# RK3566_DDR_PHY.net
KiCad netlist of a schematic drawn in Altium Designer
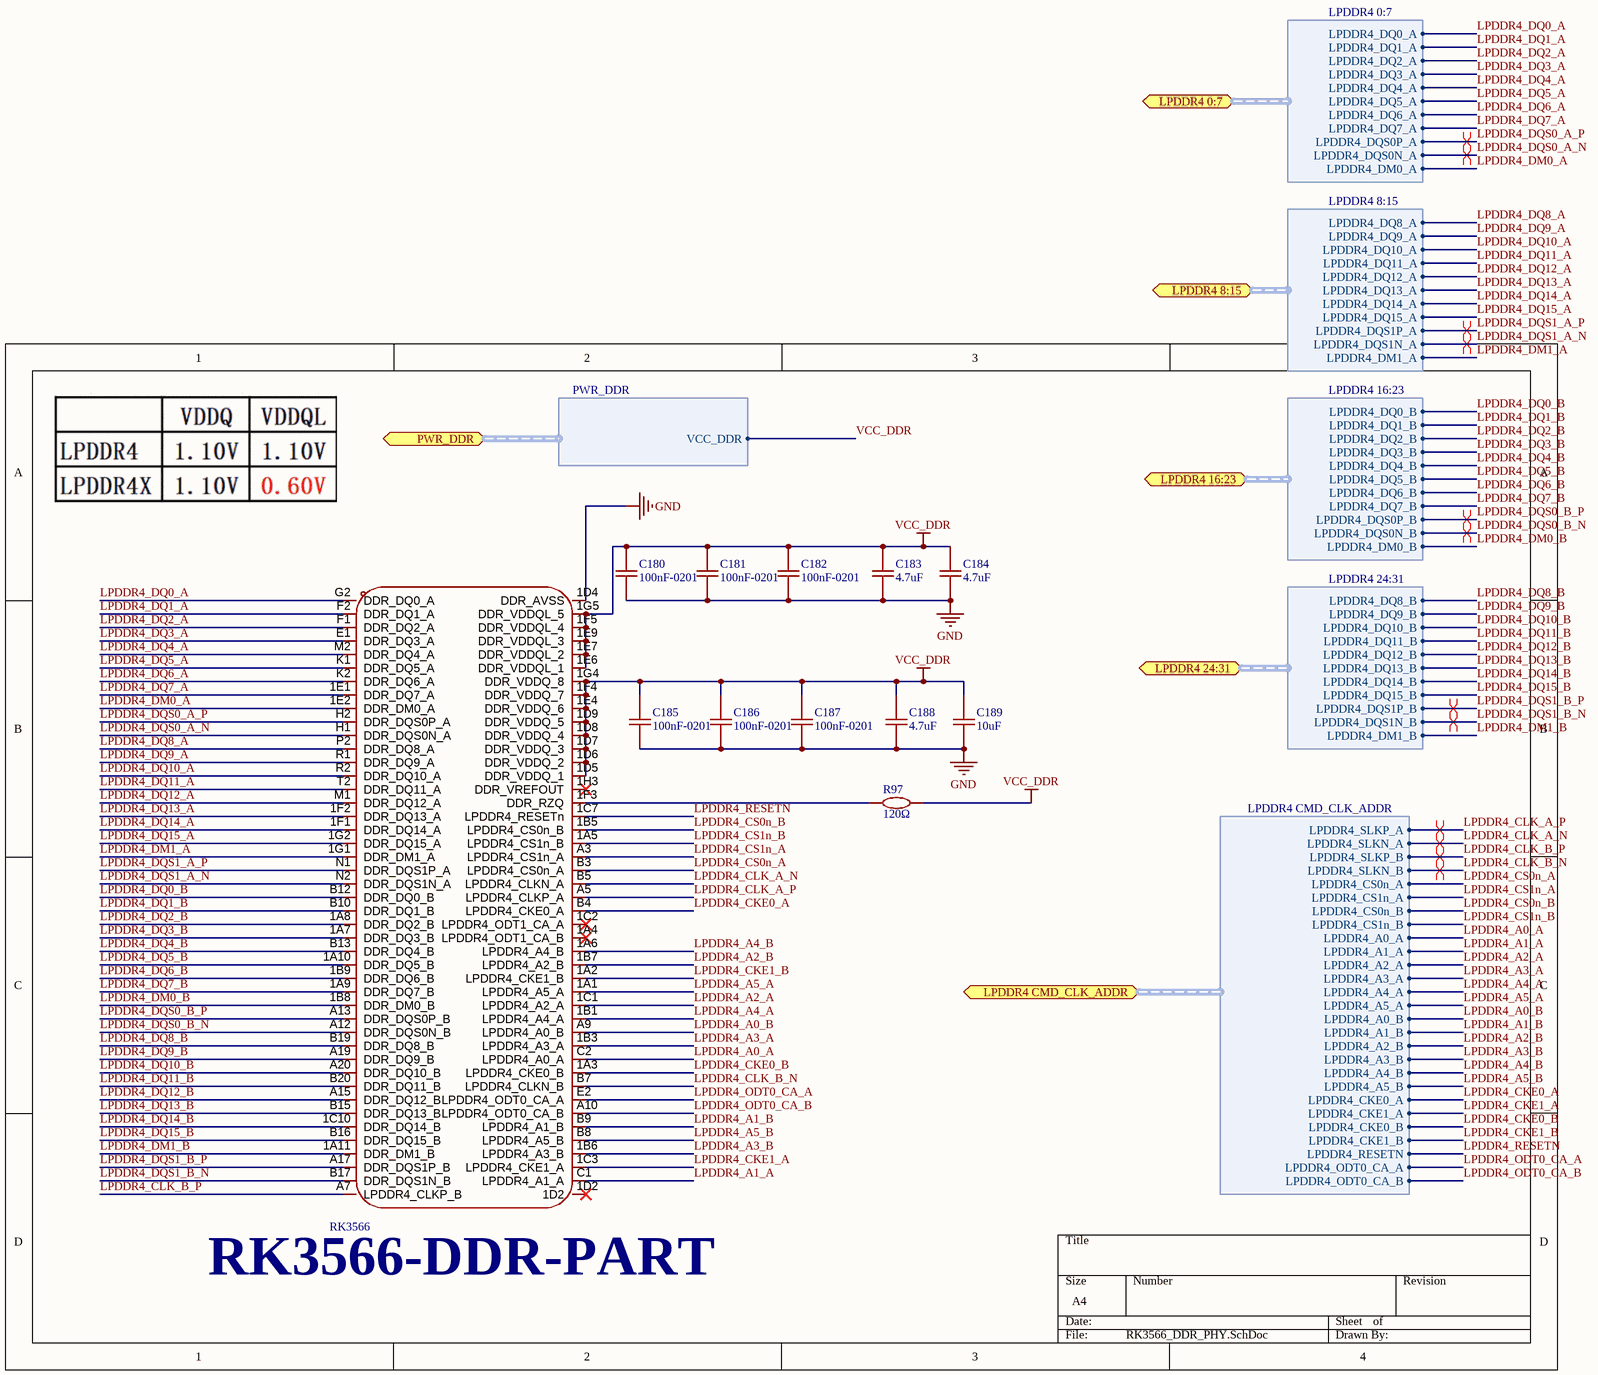
[diagram p0: RK3566_DDR_PHY.SchDoc]

(export (version "E")
  (design (tool "Eeschema 10.0.6"))
  (components
    (comp (ref "C180")
      (value "100nF-0201")
      (footprint "C0201")
      (description "CL03A104KO3NNNC")
      (libsource (lib "RLC") (part "100nF-0201"))
    )
    (comp (ref "C181")
      (value "100nF-0201")
      (footprint "C0201")
      (description "CL03A104KO3NNNC")
      (libsource (lib "RLC") (part "100nF-0201"))
    )
    (comp (ref "C182")
      (value "100nF-0201")
      (footprint "C0201")
      (description "CL03A104KO3NNNC")
      (libsource (lib "RLC") (part "100nF-0201"))
    )
    (comp (ref "C183")
      (value "4.7uF")
      (footprint "C0402")
      (description "10V 4.7uF X5R ±20% 0402 Ceramic Capacitors ROHS")
      (libsource (lib "RLC") (part "4.7uF"))
    )
    (comp (ref "C184")
      (value "4.7uF")
      (footprint "C0402")
      (description "10V 4.7uF X5R ±20% 0402 Ceramic Capacitors ROHS")
      (libsource (lib "RLC") (part "4.7uF"))
    )
    (comp (ref "C185")
      (value "100nF-0201")
      (footprint "C0201")
      (description "CL03A104KO3NNNC")
      (libsource (lib "RLC") (part "100nF-0201"))
    )
    (comp (ref "C186")
      (value "100nF-0201")
      (footprint "C0201")
      (description "CL03A104KO3NNNC")
      (libsource (lib "RLC") (part "100nF-0201"))
    )
    (comp (ref "C187")
      (value "100nF-0201")
      (footprint "C0201")
      (description "CL03A104KO3NNNC")
      (libsource (lib "RLC") (part "100nF-0201"))
    )
    (comp (ref "C188")
      (value "4.7uF")
      (footprint "C0402")
      (description "10V 4.7uF X5R ±20% 0402 Ceramic Capacitors ROHS")
      (libsource (lib "RLC") (part "4.7uF"))
    )
    (comp (ref "C189")
      (value "10uF")
      (footprint "C0603")
      (description "10V 10uF X5R ±10% 0603 Ceramic Capacitors ROHS")
      (libsource (lib "RLC") (part "10uF"))
    )
    (comp (ref "R97")
      (value "120Ω")
      (footprint "R0402")
      (description "62.5mW 120Ω 50V ±100ppm/℃ Thick Film Resistor ±1% 0402 Chip Resistor - Surface Mount ROHS")
      (libsource (lib "RLC") (part "120Ω"))
    )
    (comp (ref "U2")
      (value "RK3566")
      (footprint "BGA-565_L15.5-W14.4-P0.40_RK3566_1")
      (description "BGA-565(15.5x14.4)")
      (libsource (lib "IC") (part "RK3566"))
    )
  )
  (nets
    (net (code "8") (name "/LPDDR4_A0_A") (class "Default")
      (node (ref "U2") (pin "C2") (pinfunction "LPDDR4_A0_A_C2") (pintype "passive"))
    )
    (net (code "9") (name "/LPDDR4_A0_B") (class "Default")
      (node (ref "U2") (pin "A9") (pinfunction "LPDDR4_A0_B_A9") (pintype "passive"))
    )
    (net (code "10") (name "/LPDDR4_A1_A") (class "Default")
      (node (ref "U2") (pin "C1") (pinfunction "LPDDR4_A1_A_C1") (pintype "passive"))
    )
    (net (code "11") (name "/LPDDR4_A1_B") (class "Default")
      (node (ref "U2") (pin "B9") (pinfunction "LPDDR4_A1_B_B9") (pintype "passive"))
    )
    (net (code "12") (name "/LPDDR4_A2_A") (class "Default")
      (node (ref "U2") (pin "1C1") (pinfunction "LPDDR4_A2_A_1C1") (pintype "passive"))
    )
    (net (code "13") (name "/LPDDR4_A2_B") (class "Default")
      (node (ref "U2") (pin "1B7") (pinfunction "LPDDR4_A2_B_1B7") (pintype "passive"))
    )
    (net (code "14") (name "/LPDDR4_A3_A") (class "Default")
      (node (ref "U2") (pin "1B3") (pinfunction "LPDDR4_A3_A_1B3") (pintype "passive"))
    )
    (net (code "15") (name "/LPDDR4_A3_B") (class "Default")
      (node (ref "U2") (pin "1B6") (pinfunction "LPDDR4_A3_B_1B6") (pintype "passive"))
    )
    (net (code "16") (name "/LPDDR4_A4_A") (class "Default")
      (node (ref "U2") (pin "1B1") (pinfunction "LPDDR4_A4_A_1B1") (pintype "passive"))
    )
    (net (code "17") (name "/LPDDR4_A4_B") (class "Default")
      (node (ref "U2") (pin "1A6") (pinfunction "LPDDR4_A4_B_1A6") (pintype "passive"))
    )
    (net (code "18") (name "/LPDDR4_A5_A") (class "Default")
      (node (ref "U2") (pin "1A1") (pinfunction "LPDDR4_A5_A_1A1") (pintype "passive"))
    )
    (net (code "19") (name "/LPDDR4_A5_B") (class "Default")
      (node (ref "U2") (pin "B8") (pinfunction "LPDDR4_A5_B_B8") (pintype "passive"))
    )
    (net (code "20") (name "/LPDDR4_CKE0_A") (class "Default")
      (node (ref "U2") (pin "B4") (pinfunction "LPDDR4_CKE0_A_B4") (pintype "passive"))
    )
    (net (code "21") (name "/LPDDR4_CKE0_B") (class "Default")
      (node (ref "U2") (pin "1A3") (pinfunction "LPDDR4_CKE0_B_1A3") (pintype "passive"))
    )
    (net (code "22") (name "/LPDDR4_CKE1_A") (class "Default")
      (node (ref "U2") (pin "1C3") (pinfunction "LPDDR4_CKE1_A_1C3") (pintype "passive"))
    )
    (net (code "23") (name "/LPDDR4_CKE1_B") (class "Default")
      (node (ref "U2") (pin "1A2") (pinfunction "LPDDR4_CKE1_B_1A2") (pintype "passive"))
    )
    (net (code "24") (name "/LPDDR4_CLK_A_N") (class "Default")
      (node (ref "U2") (pin "B5") (pinfunction "LPDDR4_CLKN_A_B5") (pintype "passive"))
    )
    (net (code "25") (name "/LPDDR4_CLK_A_P") (class "Default")
      (node (ref "U2") (pin "A5") (pinfunction "LPDDR4_CLKP_A_A5") (pintype "passive"))
    )
    (net (code "26") (name "/LPDDR4_CLK_B_N") (class "Default")
      (node (ref "U2") (pin "B7") (pinfunction "LPDDR4_CLKN_B_B7") (pintype "passive"))
    )
    (net (code "27") (name "/LPDDR4_CLK_B_P") (class "Default")
      (node (ref "U2") (pin "A7") (pinfunction "LPDDR4_CLKP_B_A7") (pintype "passive"))
    )
    (net (code "28") (name "/LPDDR4_CS0n_A") (class "Default")
      (node (ref "U2") (pin "B3") (pinfunction "LPDDR4_CS0n_A_B3") (pintype "passive"))
    )
    (net (code "29") (name "/LPDDR4_CS0n_B") (class "Default")
      (node (ref "U2") (pin "1B5") (pinfunction "LPDDR4_CS0n_B_1B5") (pintype "passive"))
    )
    (net (code "30") (name "/LPDDR4_CS1n_A") (class "Default")
      (node (ref "U2") (pin "A3") (pinfunction "LPDDR4_CS1n_A_A3") (pintype "passive"))
    )
    (net (code "31") (name "/LPDDR4_CS1n_B") (class "Default")
      (node (ref "U2") (pin "1A5") (pinfunction "LPDDR4_CS1n_B_1A5") (pintype "passive"))
    )
    (net (code "32") (name "/LPDDR4_DM0_A") (class "Default")
      (node (ref "U2") (pin "1E2") (pinfunction "DDR_DM0_A_1E2") (pintype "passive"))
    )
    (net (code "33") (name "/LPDDR4_DM0_B") (class "Default")
      (node (ref "U2") (pin "1B8") (pinfunction "DDR_DM0_B_1B8") (pintype "passive"))
    )
    (net (code "34") (name "/LPDDR4_DM1_A") (class "Default")
      (node (ref "U2") (pin "1G1") (pinfunction "DDR_DM1_A_1G1") (pintype "passive"))
    )
    (net (code "35") (name "/LPDDR4_DM1_B") (class "Default")
      (node (ref "U2") (pin "1A11") (pinfunction "DDR_DM1_B_1A11") (pintype "passive"))
    )
    (net (code "36") (name "/LPDDR4_DQ0_A") (class "Default")
      (node (ref "U2") (pin "G2") (pinfunction "DDR_DQ0_A_G2") (pintype "passive"))
    )
    (net (code "37") (name "/LPDDR4_DQ0_B") (class "Default")
      (node (ref "U2") (pin "B12") (pinfunction "DDR_DQ0_B_B12") (pintype "passive"))
    )
    (net (code "38") (name "/LPDDR4_DQ1_A") (class "Default")
      (node (ref "U2") (pin "F2") (pinfunction "DDR_DQ1_A_F2") (pintype "passive"))
    )
    (net (code "39") (name "/LPDDR4_DQ1_B") (class "Default")
      (node (ref "U2") (pin "B10") (pinfunction "DDR_DQ1_B_B10") (pintype "passive"))
    )
    (net (code "40") (name "/LPDDR4_DQ2_A") (class "Default")
      (node (ref "U2") (pin "F1") (pinfunction "DDR_DQ2_A_F1") (pintype "passive"))
    )
    (net (code "41") (name "/LPDDR4_DQ2_B") (class "Default")
      (node (ref "U2") (pin "1A8") (pinfunction "DDR_DQ2_B_1A8") (pintype "passive"))
    )
    (net (code "42") (name "/LPDDR4_DQ3_A") (class "Default")
      (node (ref "U2") (pin "E1") (pinfunction "DDR_DQ3_A_E1") (pintype "passive"))
    )
    (net (code "43") (name "/LPDDR4_DQ3_B") (class "Default")
      (node (ref "U2") (pin "1A7") (pinfunction "DDR_DQ3_B_1A7") (pintype "passive"))
    )
    (net (code "44") (name "/LPDDR4_DQ4_A") (class "Default")
      (node (ref "U2") (pin "M2") (pinfunction "DDR_DQ4_A_M2") (pintype "passive"))
    )
    (net (code "45") (name "/LPDDR4_DQ4_B") (class "Default")
      (node (ref "U2") (pin "B13") (pinfunction "DDR_DQ4_B_B13") (pintype "passive"))
    )
    (net (code "46") (name "/LPDDR4_DQ5_A") (class "Default")
      (node (ref "U2") (pin "K1") (pinfunction "DDR_DQ5_A_K1") (pintype "passive"))
    )
    (net (code "47") (name "/LPDDR4_DQ5_B") (class "Default")
      (node (ref "U2") (pin "1A10") (pinfunction "DDR_DQ5_B_1A10") (pintype "passive"))
    )
    (net (code "48") (name "/LPDDR4_DQ6_A") (class "Default")
      (node (ref "U2") (pin "K2") (pinfunction "DDR_DQ6_A_K2") (pintype "passive"))
    )
    (net (code "49") (name "/LPDDR4_DQ6_B") (class "Default")
      (node (ref "U2") (pin "1B9") (pinfunction "DDR_DQ6_B_1B9") (pintype "passive"))
    )
    (net (code "50") (name "/LPDDR4_DQ7_A") (class "Default")
      (node (ref "U2") (pin "1E1") (pinfunction "DDR_DQ7_A_1E1") (pintype "passive"))
    )
    (net (code "51") (name "/LPDDR4_DQ7_B") (class "Default")
      (node (ref "U2") (pin "1A9") (pinfunction "DDR_DQ7_B_1A9") (pintype "passive"))
    )
    (net (code "52") (name "/LPDDR4_DQ8_A") (class "Default")
      (node (ref "U2") (pin "P2") (pinfunction "DDR_DQ8_A_P2") (pintype "passive"))
    )
    (net (code "53") (name "/LPDDR4_DQ8_B") (class "Default")
      (node (ref "U2") (pin "B19") (pinfunction "DDR_DQ8_B_B19") (pintype "passive"))
    )
    (net (code "54") (name "/LPDDR4_DQ9_A") (class "Default")
      (node (ref "U2") (pin "R1") (pinfunction "DDR_DQ9_A_R1") (pintype "passive"))
    )
    (net (code "55") (name "/LPDDR4_DQ9_B") (class "Default")
      (node (ref "U2") (pin "A19") (pinfunction "DDR_DQ9_B_A19") (pintype "passive"))
    )
    (net (code "56") (name "/LPDDR4_DQ10_A") (class "Default")
      (node (ref "U2") (pin "R2") (pinfunction "DDR_DQ10_A_R2") (pintype "passive"))
    )
    (net (code "57") (name "/LPDDR4_DQ10_B") (class "Default")
      (node (ref "U2") (pin "A20") (pinfunction "DDR_DQ10_B_A20") (pintype "passive"))
    )
    (net (code "58") (name "/LPDDR4_DQ11_A") (class "Default")
      (node (ref "U2") (pin "T2") (pinfunction "DDR_DQ11_A_T2") (pintype "passive"))
    )
    (net (code "59") (name "/LPDDR4_DQ11_B") (class "Default")
      (node (ref "U2") (pin "B20") (pinfunction "DDR_DQ11_B_B20") (pintype "passive"))
    )
    (net (code "60") (name "/LPDDR4_DQ12_A") (class "Default")
      (node (ref "U2") (pin "M1") (pinfunction "DDR_DQ12_A_M1") (pintype "passive"))
    )
    (net (code "61") (name "/LPDDR4_DQ12_B") (class "Default")
      (node (ref "U2") (pin "A15") (pinfunction "DDR_DQ12_B_A15") (pintype "passive"))
    )
    (net (code "62") (name "/LPDDR4_DQ13_A") (class "Default")
      (node (ref "U2") (pin "1F2") (pinfunction "DDR_DQ13_A_1F2") (pintype "passive"))
    )
    (net (code "63") (name "/LPDDR4_DQ13_B") (class "Default")
      (node (ref "U2") (pin "B15") (pinfunction "DDR_DQ13_B_B15") (pintype "passive"))
    )
    (net (code "64") (name "/LPDDR4_DQ14_A") (class "Default")
      (node (ref "U2") (pin "1F1") (pinfunction "DDR_DQ14_A_1F1") (pintype "passive"))
    )
    (net (code "65") (name "/LPDDR4_DQ14_B") (class "Default")
      (node (ref "U2") (pin "1C10") (pinfunction "DDR_DQ14_B_1C10") (pintype "passive"))
    )
    (net (code "66") (name "/LPDDR4_DQ15_A") (class "Default")
      (node (ref "U2") (pin "1G2") (pinfunction "DDR_DQ15_A_1G2") (pintype "passive"))
    )
    (net (code "67") (name "/LPDDR4_DQ15_B") (class "Default")
      (node (ref "U2") (pin "B16") (pinfunction "DDR_DQ15_B_B16") (pintype "passive"))
    )
    (net (code "68") (name "/LPDDR4_DQS0_A_N") (class "Default")
      (node (ref "U2") (pin "H1") (pinfunction "DDR_DQS0N_A_H1") (pintype "passive"))
    )
    (net (code "69") (name "/LPDDR4_DQS0_A_P") (class "Default")
      (node (ref "U2") (pin "H2") (pinfunction "DDR_DQS0P_A_H2") (pintype "passive"))
    )
    (net (code "70") (name "/LPDDR4_DQS0_B_N") (class "Default")
      (node (ref "U2") (pin "A12") (pinfunction "DDR_DQS0N_B_A12") (pintype "passive"))
    )
    (net (code "71") (name "/LPDDR4_DQS0_B_P") (class "Default")
      (node (ref "U2") (pin "A13") (pinfunction "DDR_DQS0P_B_A13") (pintype "passive"))
    )
    (net (code "72") (name "/LPDDR4_DQS1_A_N") (class "Default")
      (node (ref "U2") (pin "N2") (pinfunction "DDR_DQS1N_A_N2") (pintype "passive"))
    )
    (net (code "73") (name "/LPDDR4_DQS1_A_P") (class "Default")
      (node (ref "U2") (pin "N1") (pinfunction "DDR_DQS1P_A_N1") (pintype "passive"))
    )
    (net (code "74") (name "/LPDDR4_DQS1_B_N") (class "Default")
      (node (ref "U2") (pin "B17") (pinfunction "DDR_DQS1N_B_B17") (pintype "passive"))
    )
    (net (code "75") (name "/LPDDR4_DQS1_B_P") (class "Default")
      (node (ref "U2") (pin "A17") (pinfunction "DDR_DQS1P_B_A17") (pintype "passive"))
    )
    (net (code "76") (name "/LPDDR4_ODT0_CA_A") (class "Default")
      (node (ref "U2") (pin "E2") (pinfunction "LPDDR4_ODT0_CA_A_E2") (pintype "passive"))
    )
    (net (code "77") (name "/LPDDR4_ODT0_CA_B") (class "Default")
      (node (ref "U2") (pin "A10") (pinfunction "LPDDR4_ODT0_CA_B_A10") (pintype "passive"))
    )
    (net (code "78") (name "/LPDDR4_RESETN") (class "Default")
      (node (ref "U2") (pin "1C7") (pinfunction "LPDDR4_RESETn_1C7") (pintype "passive"))
    )
    (net (code "85") (name "GND") (class "Default")
      (node (ref "C180") (pin "1") (pinfunction "1_1") (pintype "passive"))
      (node (ref "C181") (pin "1") (pinfunction "1_1") (pintype "passive"))
      (node (ref "C182") (pin "1") (pinfunction "1_1") (pintype "passive"))
      (node (ref "C183") (pin "1") (pinfunction "1_1") (pintype "passive"))
      (node (ref "C184") (pin "1") (pinfunction "1_1") (pintype "passive"))
      (node (ref "C185") (pin "1") (pinfunction "1_1") (pintype "passive"))
      (node (ref "C186") (pin "1") (pinfunction "1_1") (pintype "passive"))
      (node (ref "C187") (pin "1") (pinfunction "1_1") (pintype "passive"))
      (node (ref "C188") (pin "1") (pinfunction "1_1") (pintype "passive"))
      (node (ref "C189") (pin "1") (pinfunction "1_1") (pintype "passive"))
      (node (ref "U2") (pin "1D4") (pinfunction "DDR_AVSS_1D4") (pintype "passive"))
    )
    (net (code "86") (name "Net-(U2C-DDR_RZQ)") (class "Default")
      (node (ref "R97") (pin "1") (pinfunction "1_1") (pintype "passive"))
      (node (ref "U2") (pin "1F3") (pinfunction "DDR_RZQ_1F3") (pintype "passive"))
    )
    (net (code "87") (name "VCC_DDR") (class "Default")
      (node (ref "C180") (pin "2") (pinfunction "2_2") (pintype "passive"))
      (node (ref "C181") (pin "2") (pinfunction "2_2") (pintype "passive"))
      (node (ref "C182") (pin "2") (pinfunction "2_2") (pintype "passive"))
      (node (ref "C183") (pin "2") (pinfunction "2_2") (pintype "passive"))
      (node (ref "C184") (pin "2") (pinfunction "2_2") (pintype "passive"))
      (node (ref "C185") (pin "2") (pinfunction "2_2") (pintype "passive"))
      (node (ref "C186") (pin "2") (pinfunction "2_2") (pintype "passive"))
      (node (ref "C187") (pin "2") (pinfunction "2_2") (pintype "passive"))
      (node (ref "C188") (pin "2") (pinfunction "2_2") (pintype "passive"))
      (node (ref "C189") (pin "2") (pinfunction "2_2") (pintype "passive"))
      (node (ref "R97") (pin "2") (pinfunction "2_2") (pintype "passive"))
      (node (ref "U2") (pin "1D5") (pinfunction "DDR_VDDQ_1_1D5") (pintype "passive"))
      (node (ref "U2") (pin "1D6") (pinfunction "DDR_VDDQ_2_1D6") (pintype "passive"))
      (node (ref "U2") (pin "1D7") (pinfunction "DDR_VDDQ_3_1D7") (pintype "passive"))
      (node (ref "U2") (pin "1D8") (pinfunction "DDR_VDDQ_4_1D8") (pintype "passive"))
      (node (ref "U2") (pin "1D9") (pinfunction "DDR_VDDQ_5_1D9") (pintype "passive"))
      (node (ref "U2") (pin "1E4") (pinfunction "DDR_VDDQ_6_1E4") (pintype "passive"))
      (node (ref "U2") (pin "1E6") (pinfunction "DDR_VDDQL_1_1E6") (pintype "passive"))
      (node (ref "U2") (pin "1E7") (pinfunction "DDR_VDDQL_2_1E7") (pintype "passive"))
      (node (ref "U2") (pin "1E9") (pinfunction "DDR_VDDQL_3_1E9") (pintype "passive"))
      (node (ref "U2") (pin "1F4") (pinfunction "DDR_VDDQ_7_1F4") (pintype "passive"))
      (node (ref "U2") (pin "1F5") (pinfunction "DDR_VDDQL_4_1F5") (pintype "passive"))
      (node (ref "U2") (pin "1G4") (pinfunction "DDR_VDDQ_8_1G4") (pintype "passive"))
      (node (ref "U2") (pin "1G5") (pinfunction "DDR_VDDQL_5_1G5") (pintype "passive"))
    )
    (net (code "88") (name "unconnected-(U2-Pad1D2)") (class "Default")
      (node (ref "U2") (pin "1D2") (pinfunction "1D2_1D2") (pintype "passive+no_connect"))
    )
    (net (code "89") (name "unconnected-(U2C-DDR_VREFOUT-Pad1H3)") (class "Default")
      (node (ref "U2") (pin "1H3") (pinfunction "DDR_VREFOUT_1H3") (pintype "passive+no_connect"))
    )
    (net (code "90") (name "unconnected-(U2C-LPDDR4_ODT1_CA_A-Pad1C2)") (class "Default")
      (node (ref "U2") (pin "1C2") (pinfunction "LPDDR4_ODT1_CA_A_1C2") (pintype "passive+no_connect"))
    )
    (net (code "91") (name "unconnected-(U2C-LPDDR4_ODT1_CA_B-Pad1A4)") (class "Default")
      (node (ref "U2") (pin "1A4") (pinfunction "LPDDR4_ODT1_CA_B_1A4") (pintype "passive+no_connect"))
    )
  )
)
